# SCIR_RPi_COM.net
KiCad netlist of a schematic drawn in EAGLE
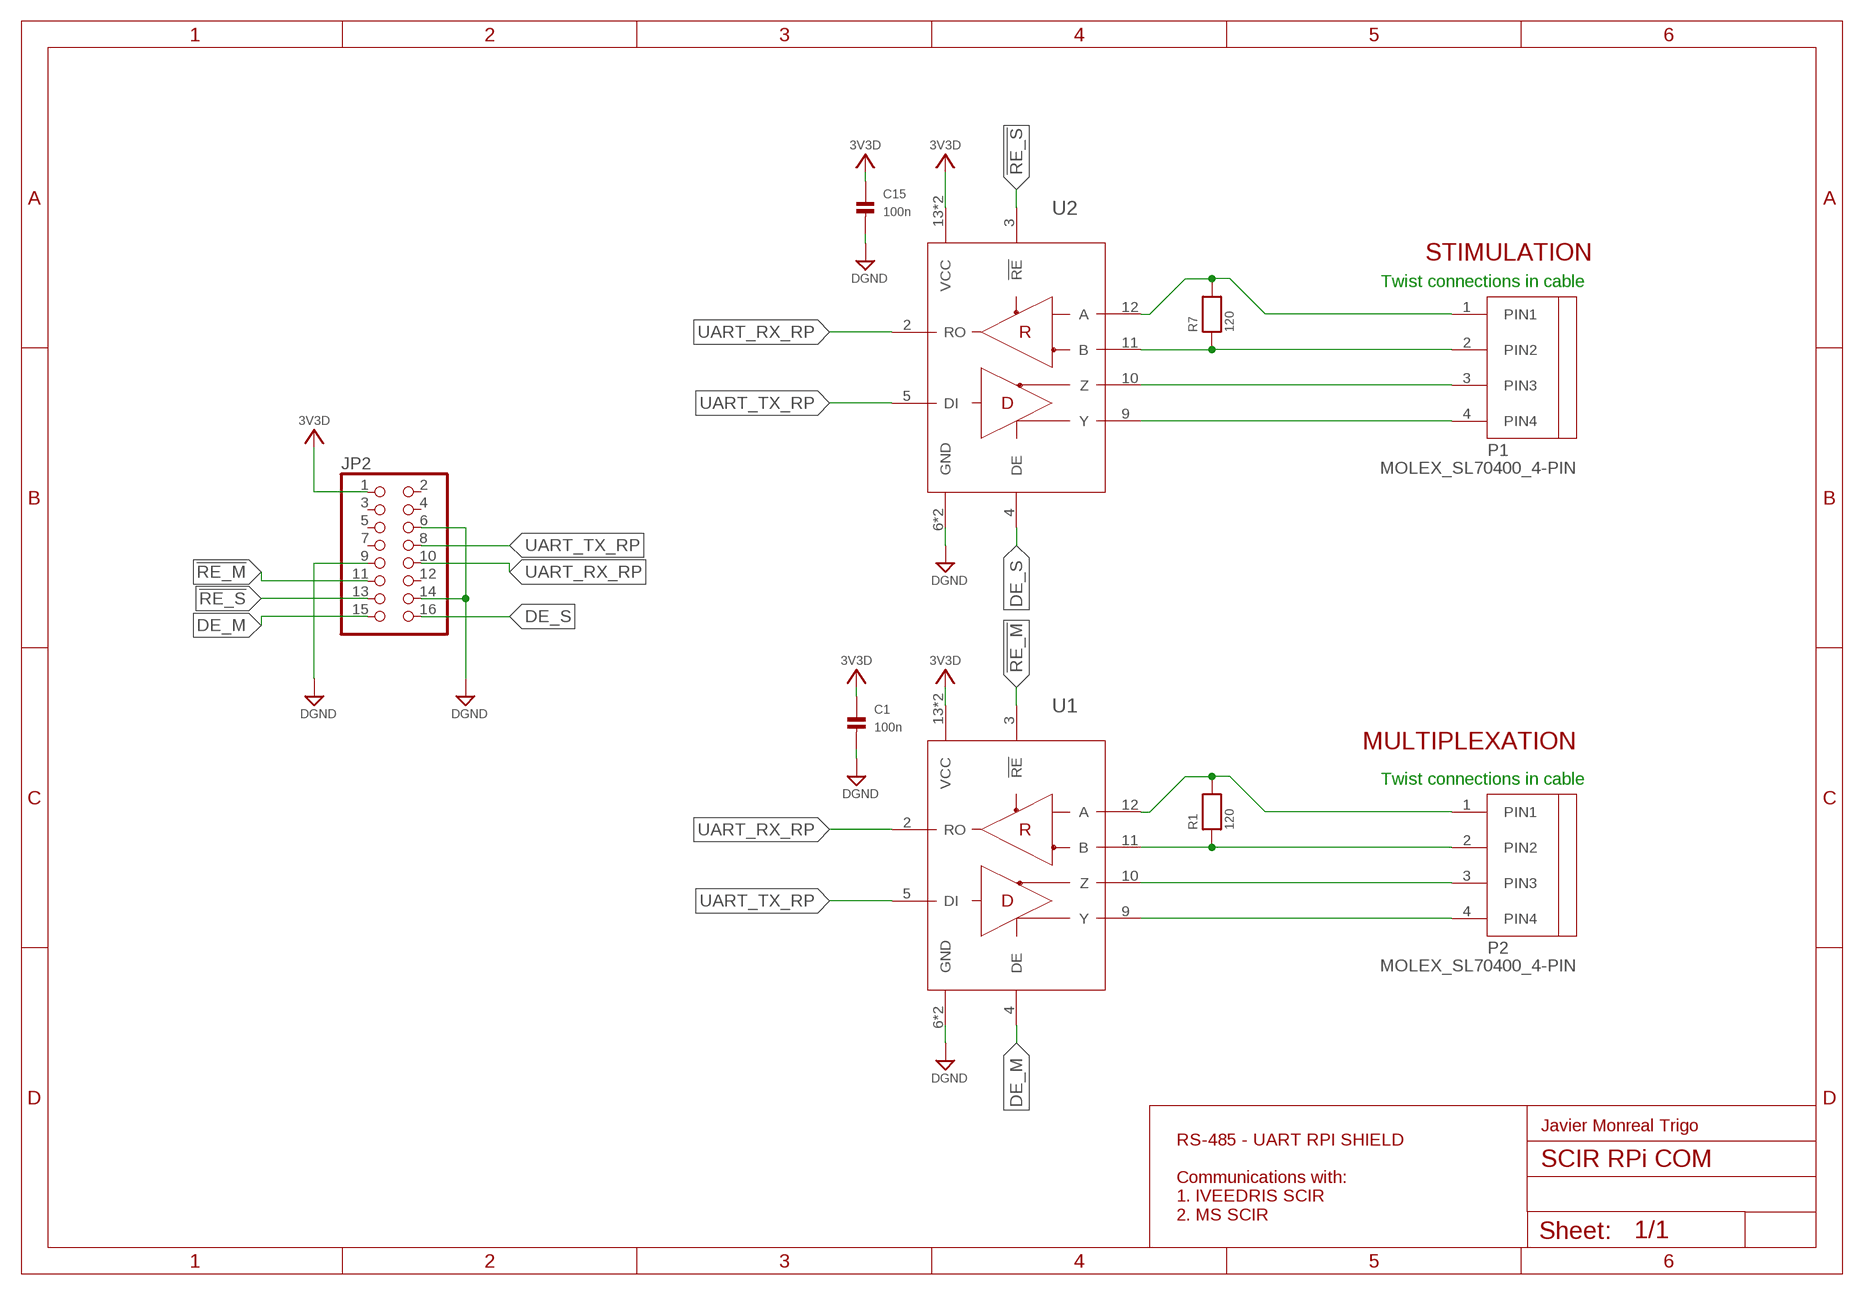
[diagram p0: schematic, sheet 1]

(export (version "E")
  (design (tool "Eeschema 10.0.6"))
  (components
    (comp (ref "C1")
      (value "100n")
      (footprint "eagle-import:0805")
      (libsource (lib "eagle-import") (part "CAP_CERAMIC0805"))
    )
    (comp (ref "C15")
      (value "100n")
      (footprint "eagle-import:0805")
      (libsource (lib "eagle-import") (part "CAP_CERAMIC0805"))
    )
    (comp (ref "JP2")
      (value "HEADER-2X8")
      (footprint "eagle-import:2X08")
      (libsource (lib "eagle-import") (part "HEADER-2X8"))
    )
    (comp (ref "P1")
      (value "MOLEX_SL70400_4-PIN")
      (footprint "eagle-import:MOLEX_SL70400_4-PIN")
      (fields (field (name "MANUFACTURER_PART_NUMBER") "0705530038"))
      (libsource (lib "eagle-import") (part "MOLEX_SL70400_4-PIN"))
    )
    (comp (ref "P2")
      (value "MOLEX_SL70400_4-PIN")
      (footprint "eagle-import:MOLEX_SL70400_4-PIN")
      (fields (field (name "MANUFACTURER_PART_NUMBER") "0705530038"))
      (libsource (lib "eagle-import") (part "MOLEX_SL70400_4-PIN"))
    )
    (comp (ref "R1")
      (value "120")
      (footprint "eagle-import:0805")
      (libsource (lib "eagle-import") (part "RESISTOR0805"))
    )
    (comp (ref "R7")
      (value "120")
      (footprint "eagle-import:0805")
      (libsource (lib "eagle-import") (part "RESISTOR0805"))
    )
    (comp (ref "U1")
      (value "MAX3491ECSD+")
      (footprint "eagle-import:SO14")
      (libsource (lib "eagle-import") (part "MAX3491ECSD+"))
    )
    (comp (ref "U2")
      (value "MAX3491ECSD+")
      (footprint "eagle-import:SO14")
      (libsource (lib "eagle-import") (part "MAX3491ECSD+"))
    )
  )
  (nets
    (net (code "1") (name "/~{RE_M}") (class "Default")
      (node (ref "JP2") (pin "11") (pinfunction "11_11") (pintype "passive"))
      (node (ref "U1") (pin "3") (pinfunction "~{RE}_3") (pintype "input"))
    )
    (net (code "2") (name "/~{RE_S}") (class "Default")
      (node (ref "JP2") (pin "13") (pinfunction "13_13") (pintype "passive"))
      (node (ref "U2") (pin "3") (pinfunction "~{RE}_3") (pintype "input"))
    )
    (net (code "3") (name "3V3D") (class "Default")
      (node (ref "C1") (pin "1") (pinfunction "P$1_1") (pintype "passive"))
      (node (ref "C15") (pin "1") (pinfunction "P$1_1") (pintype "passive"))
      (node (ref "JP2") (pin "1") (pinfunction "1_1") (pintype "passive"))
      (node (ref "U1") (pin "13") (pinfunction "VCC_13") (pintype "power_in"))
      (node (ref "U1") (pin "14") (pinfunction "VCC_14") (pintype "power_in"))
      (node (ref "U2") (pin "13") (pinfunction "VCC_13") (pintype "power_in"))
      (node (ref "U2") (pin "14") (pinfunction "VCC_14") (pintype "power_in"))
    )
    (net (code "4") (name "DE_M") (class "Default")
      (node (ref "JP2") (pin "15") (pinfunction "15_15") (pintype "passive"))
      (node (ref "U1") (pin "4") (pinfunction "DE_4") (pintype "input"))
    )
    (net (code "5") (name "DE_S") (class "Default")
      (node (ref "JP2") (pin "16") (pinfunction "16_16") (pintype "passive"))
      (node (ref "U2") (pin "4") (pinfunction "DE_4") (pintype "input"))
    )
    (net (code "6") (name "DGND") (class "Default")
      (node (ref "C1") (pin "2") (pinfunction "P$2_2") (pintype "passive"))
      (node (ref "C15") (pin "2") (pinfunction "P$2_2") (pintype "passive"))
      (node (ref "JP2") (pin "14") (pinfunction "14_14") (pintype "passive"))
      (node (ref "JP2") (pin "6") (pinfunction "6_6") (pintype "passive"))
      (node (ref "JP2") (pin "9") (pinfunction "9_9") (pintype "passive"))
      (node (ref "U1") (pin "6") (pinfunction "GND_6") (pintype "power_in"))
      (node (ref "U1") (pin "7") (pinfunction "GND_7") (pintype "power_in"))
      (node (ref "U2") (pin "6") (pinfunction "GND_6") (pintype "power_in"))
      (node (ref "U2") (pin "7") (pinfunction "GND_7") (pintype "power_in"))
    )
    (net (code "7") (name "Net-(P1-PIN1)") (class "Default")
      (node (ref "P1") (pin "1") (pinfunction "PIN1_1") (pintype "bidirectional"))
      (node (ref "R7") (pin "2") (pinfunction "2_2") (pintype "passive"))
      (node (ref "U2") (pin "12") (pinfunction "A_12") (pintype "input"))
    )
    (net (code "8") (name "Net-(P1-PIN2)") (class "Default")
      (node (ref "P1") (pin "2") (pinfunction "PIN2_2") (pintype "bidirectional"))
      (node (ref "R7") (pin "1") (pinfunction "1_1") (pintype "passive"))
      (node (ref "U2") (pin "11") (pinfunction "B_11") (pintype "input"))
    )
    (net (code "9") (name "Net-(P1-PIN3)") (class "Default")
      (node (ref "P1") (pin "3") (pinfunction "PIN3_3") (pintype "bidirectional"))
      (node (ref "U2") (pin "10") (pinfunction "Z_10") (pintype "output"))
    )
    (net (code "10") (name "Net-(P1-PIN4)") (class "Default")
      (node (ref "P1") (pin "4") (pinfunction "PIN4_4") (pintype "bidirectional"))
      (node (ref "U2") (pin "9") (pinfunction "Y_9") (pintype "output"))
    )
    (net (code "11") (name "Net-(P2-PIN1)") (class "Default")
      (node (ref "P2") (pin "1") (pinfunction "PIN1_1") (pintype "bidirectional"))
      (node (ref "R1") (pin "2") (pinfunction "2_2") (pintype "passive"))
      (node (ref "U1") (pin "12") (pinfunction "A_12") (pintype "input"))
    )
    (net (code "12") (name "Net-(P2-PIN2)") (class "Default")
      (node (ref "P2") (pin "2") (pinfunction "PIN2_2") (pintype "bidirectional"))
      (node (ref "R1") (pin "1") (pinfunction "1_1") (pintype "passive"))
      (node (ref "U1") (pin "11") (pinfunction "B_11") (pintype "input"))
    )
    (net (code "13") (name "Net-(P2-PIN3)") (class "Default")
      (node (ref "P2") (pin "3") (pinfunction "PIN3_3") (pintype "bidirectional"))
      (node (ref "U1") (pin "10") (pinfunction "Z_10") (pintype "output"))
    )
    (net (code "14") (name "Net-(P2-PIN4)") (class "Default")
      (node (ref "P2") (pin "4") (pinfunction "PIN4_4") (pintype "bidirectional"))
      (node (ref "U1") (pin "9") (pinfunction "Y_9") (pintype "output"))
    )
    (net (code "15") (name "UART_RX_RP") (class "Default")
      (node (ref "JP2") (pin "10") (pinfunction "10_10") (pintype "passive"))
      (node (ref "U1") (pin "2") (pinfunction "RO_2") (pintype "output"))
      (node (ref "U2") (pin "2") (pinfunction "RO_2") (pintype "output"))
    )
    (net (code "16") (name "UART_TX_RP") (class "Default")
      (node (ref "JP2") (pin "8") (pinfunction "8_8") (pintype "passive"))
      (node (ref "U1") (pin "5") (pinfunction "DI_5") (pintype "input"))
      (node (ref "U2") (pin "5") (pinfunction "DI_5") (pintype "input"))
    )
    (net (code "17") (name "unconnected-(JP2-Pad2)") (class "Default")
      (node (ref "JP2") (pin "2") (pinfunction "2_2") (pintype "passive"))
    )
    (net (code "18") (name "unconnected-(JP2-Pad3)") (class "Default")
      (node (ref "JP2") (pin "3") (pinfunction "3_3") (pintype "passive"))
    )
    (net (code "19") (name "unconnected-(JP2-Pad4)") (class "Default")
      (node (ref "JP2") (pin "4") (pinfunction "4_4") (pintype "passive"))
    )
    (net (code "20") (name "unconnected-(JP2-Pad5)") (class "Default")
      (node (ref "JP2") (pin "5") (pinfunction "5_5") (pintype "passive"))
    )
    (net (code "21") (name "unconnected-(JP2-Pad7)") (class "Default")
      (node (ref "JP2") (pin "7") (pinfunction "7_7") (pintype "passive"))
    )
    (net (code "22") (name "unconnected-(JP2-Pad12)") (class "Default")
      (node (ref "JP2") (pin "12") (pinfunction "12_12") (pintype "passive"))
    )
  )
)
